# Power.net
KiCad netlist of a schematic drawn in Altium Designer
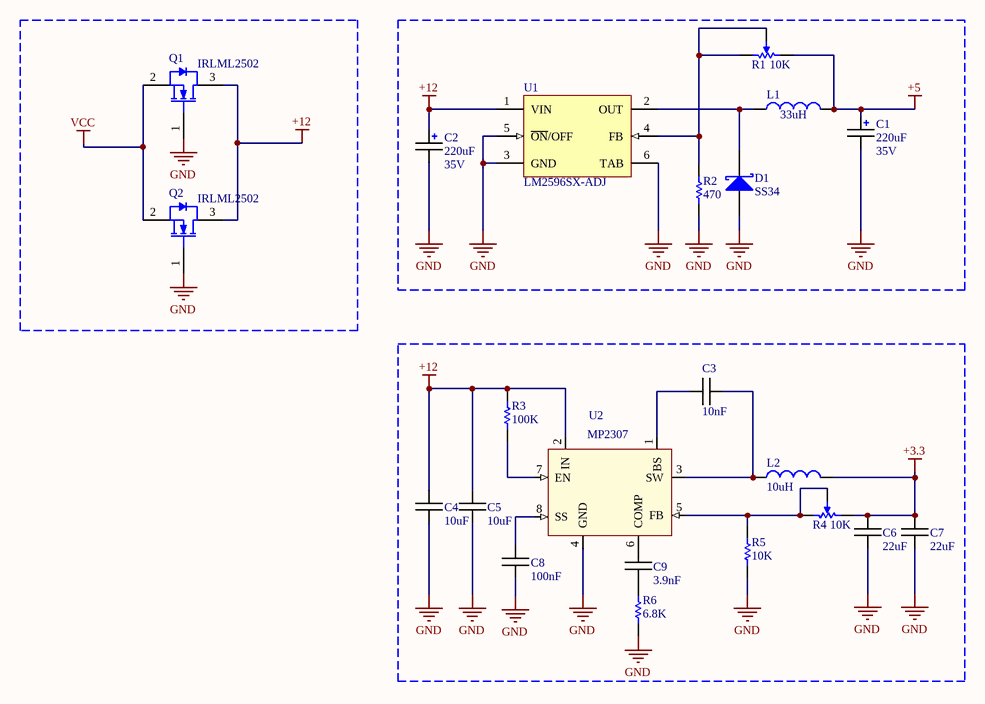
[diagram p0: Power.SchDoc]

(export (version "E")
  (design (tool "Eeschema 10.0.6"))
  (components
    (comp (ref "C1")
      (value "CAP_ELEC_SMD")
      (footprint "ECAP_SMD_8mmx10mm")
      (fields (field (name "RATED CAPACITANCE") "220uF") (field (name "RATED VOLTAGE") "35V"))
      (libsource (lib "altium-import") (part "root_3_CAP_ELEC_SMD_"))
    )
    (comp (ref "C2")
      (value "CAP_ELEC_SMD")
      (footprint "ECAP_SMD_8mmx10mm")
      (fields (field (name "RATED CAPACITANCE") "220uF") (field (name "RATED VOLTAGE") "35V"))
      (libsource (lib "altium-import") (part "root_3_CAP_ELEC_SMD_"))
    )
    (comp (ref "C3")
      (value "CAP_SMD")
      (footprint "CAP0805")
      (description "Ceramic capacitor, 0805")
      (fields (field (name "VAL") "10nF"))
      (libsource (lib "altium-import") (part "root_0_CAP_SMD_"))
    )
    (comp (ref "C4")
      (value "CAP_SMD")
      (footprint "CAPC1206(3216)170_L")
      (description "Ceramic capacitor, 0805")
      (fields (field (name "VAL") "10uF"))
      (libsource (lib "altium-import") (part "root_1_CAP_SMD_"))
    )
    (comp (ref "C5")
      (value "CAP_SMD")
      (footprint "CAPC1206(3216)170_L")
      (description "Ceramic capacitor, 0805")
      (fields (field (name "VAL") "10uF"))
      (libsource (lib "altium-import") (part "root_1_CAP_SMD_"))
    )
    (comp (ref "C6")
      (value "CAP_SMD")
      (footprint "CAPC1206(3216)170_L")
      (description "Ceramic capacitor, 0805")
      (fields (field (name "VAL") "22uF"))
      (libsource (lib "altium-import") (part "root_1_CAP_SMD_"))
    )
    (comp (ref "C7")
      (value "CAP_SMD")
      (footprint "CAPC1206(3216)170_L")
      (description "Ceramic capacitor, 0805")
      (fields (field (name "VAL") "22uF"))
      (libsource (lib "altium-import") (part "root_1_CAP_SMD_"))
    )
    (comp (ref "C8")
      (value "CAP_SMD")
      (footprint "CAP0805")
      (description "Ceramic capacitor, 0805")
      (fields (field (name "VAL") "100nF"))
      (libsource (lib "altium-import") (part "root_1_CAP_SMD_"))
    )
    (comp (ref "C9")
      (value "CAP_SMD")
      (footprint "CAP0805")
      (description "Ceramic capacitor, 0805")
      (fields (field (name "VAL") "3.9nF"))
      (libsource (lib "altium-import") (part "root_1_CAP_SMD_"))
    )
    (comp (ref "D1")
      (value "SS34")
      (footprint "DO-214")
      (description "Schottky Rectifier")
      (libsource (lib "altium-import") (part "root_1_SS34_"))
    )
    (comp (ref "L1")
      (value "~")
      (footprint "SDR1006_SMD")
      (description "Inductor for Power Circuits")
      (fields
        (field (name "INDUCTANCE") "33uH")
        (field (name "TOLERANCE") "±30%")
        (field (name "MANUFACTURER") "TDK")
      )
      (libsource (lib "altium-import") (part "root_0_Inductor power_"))
    )
    (comp (ref "L2")
      (value "10uH")
      (footprint "IHLP2525")
      (description "Inductor for Power Circuits")
      (fields (field (name "Comment") "Inductor power"))
      (libsource (lib "altium-import") (part "root_0_Inductor power_"))
    )
    (comp (ref "Q1")
      (value "IRLML2502")
      (footprint "SOT23_L")
      (description "N-Channel HEXFET(R) Power MOSFET, 20 V VDS, +/- 12 V VGS, 4.2 A, 3-Pin SOT23, RoHS, Tape and Reel")
      (fields (field (name "MANUFACTURER") "International Rectifier"))
      (libsource (lib "web.skorpio") (part "IRLML2502"))
    )
    (comp (ref "Q2")
      (value "IRLML2502")
      (footprint "SOT23_L")
      (description "N-Channel HEXFET(R) Power MOSFET, 20 V VDS, +/- 12 V VGS, 4.2 A, 3-Pin SOT23, RoHS, Tape and Reel")
      (fields (field (name "MANUFACTURER") "International Rectifier"))
      (libsource (lib "web.skorpio") (part "IRLML2502"))
    )
    (comp (ref "R1")
      (value "10K")
      (footprint "BOUR-3296W")
      (fields (field (name "Comment") "3296W"))
      (libsource (lib "altium-import") (part "root_2_mirrored_Potentiometer_"))
    )
    (comp (ref "R2")
      (value "RES_SMD")
      (footprint "RES0805")
      (fields (field (name "VAL") "470"))
      (libsource (lib "altium-import") (part "root_1_RES_SMD_"))
    )
    (comp (ref "R3")
      (value "RES_SMD")
      (footprint "RES0805")
      (fields (field (name "VAL") "100K"))
      (libsource (lib "altium-import") (part "root_1_RES_SMD_"))
    )
    (comp (ref "R4")
      (value "10K")
      (footprint "BOUR-3296W")
      (fields (field (name "Comment") "3296W"))
      (libsource (lib "altium-import") (part "root_2_mirrored_Potentiometer_"))
    )
    (comp (ref "R5")
      (value "RES_SMD")
      (footprint "RES0805")
      (fields (field (name "VAL") "10K"))
      (libsource (lib "altium-import") (part "root_1_RES_SMD_"))
    )
    (comp (ref "R6")
      (value "RES_SMD")
      (footprint "RES0805")
      (fields (field (name "VAL") "6.8K"))
      (libsource (lib "altium-import") (part "root_1_RES_SMD_"))
    )
    (comp (ref "U1")
      (value "LM2596SX-ADJ")
      (footprint "KTT0005B_N")
      (description "SIMPLE SWITCHER® Power Converter 150 KHz 3A Step-Down Voltage Regulator, 5-pin TO-263")
      (fields (field (name "MANUFACTURER") "Texas Instruments"))
      (libsource (lib "altium-import") (part "root_0_LM2596SX-ADJ_"))
    )
    (comp (ref "U2")
      (value "MP2307")
      (footprint "SOIC8N")
      (description "Monolithic synchronous buck regulator")
      (libsource (lib "altium-import") (part "root_0_MP2307_"))
    )
  )
  (nets
    (net (code "1") (name "+3.3") (class "Default")
      (node (ref "C6") (pin "2") (pinfunction "2_2") (pintype "passive"))
      (node (ref "C7") (pin "2") (pinfunction "2_2") (pintype "passive"))
      (node (ref "L2") (pin "2") (pinfunction "2_2") (pintype "passive"))
      (node (ref "R4") (pin "3") (pinfunction "3_3") (pintype "passive"))
    )
    (net (code "2") (name "+5") (class "Default")
      (node (ref "C1") (pin "1") (pinfunction "1_1") (pintype "passive"))
      (node (ref "L1") (pin "2") (pinfunction "2_2") (pintype "passive"))
      (node (ref "R1") (pin "3") (pinfunction "3_3") (pintype "passive"))
    )
    (net (code "3") (name "+12") (class "Default")
      (node (ref "C2") (pin "1") (pinfunction "1_1") (pintype "passive"))
      (node (ref "C4") (pin "2") (pinfunction "2_2") (pintype "passive"))
      (node (ref "C5") (pin "2") (pinfunction "2_2") (pintype "passive"))
      (node (ref "Q1") (pin "3") (pinfunction "D_3") (pintype "passive"))
      (node (ref "Q2") (pin "3") (pinfunction "D_3") (pintype "passive"))
      (node (ref "R3") (pin "2") (pinfunction "2_2") (pintype "passive"))
      (node (ref "U1") (pin "1") (pinfunction "VIN_1") (pintype "power_in"))
      (node (ref "U2") (pin "2") (pinfunction "IN_2") (pintype "passive"))
    )
    (net (code "4") (name "GND") (class "Default")
      (node (ref "C1") (pin "2") (pinfunction "2_2") (pintype "passive"))
      (node (ref "C2") (pin "2") (pinfunction "2_2") (pintype "passive"))
      (node (ref "C4") (pin "1") (pinfunction "1_1") (pintype "passive"))
      (node (ref "C5") (pin "1") (pinfunction "1_1") (pintype "passive"))
      (node (ref "C6") (pin "1") (pinfunction "1_1") (pintype "passive"))
      (node (ref "C7") (pin "1") (pinfunction "1_1") (pintype "passive"))
      (node (ref "C8") (pin "1") (pinfunction "1_1") (pintype "passive"))
      (node (ref "D1") (pin "2") (pinfunction "A_2") (pintype "passive"))
      (node (ref "Q1") (pin "1") (pinfunction "G_1") (pintype "passive"))
      (node (ref "Q2") (pin "1") (pinfunction "G_1") (pintype "passive"))
      (node (ref "R2") (pin "1") (pinfunction "1_1") (pintype "passive"))
      (node (ref "R5") (pin "1") (pinfunction "1_1") (pintype "passive"))
      (node (ref "R6") (pin "1") (pinfunction "1_1") (pintype "passive"))
      (node (ref "U1") (pin "3") (pinfunction "GND_3") (pintype "power_in"))
      (node (ref "U1") (pin "5") (pinfunction "~{ON}/OFF_5") (pintype "input"))
      (node (ref "U1") (pin "6") (pinfunction "TAB_6") (pintype "power_in"))
      (node (ref "U2") (pin "4") (pinfunction "GND_4") (pintype "passive"))
    )
    (net (code "5") (name "Net-(C9-Pad1)") (class "Default")
      (node (ref "C9") (pin "1") (pinfunction "1_1") (pintype "passive"))
      (node (ref "R6") (pin "2") (pinfunction "2_2") (pintype "passive"))
    )
    (net (code "6") (name "Net-(D1-K)") (class "Default")
      (node (ref "D1") (pin "1") (pinfunction "K_1") (pintype "passive"))
      (node (ref "L1") (pin "1") (pinfunction "1_1") (pintype "passive"))
      (node (ref "U1") (pin "2") (pinfunction "OUT_2") (pintype "power_in"))
    )
    (net (code "7") (name "Net-(U1-FB)") (class "Default")
      (node (ref "R1") (pin "1") (pinfunction "1_1") (pintype "passive"))
      (node (ref "R1") (pin "2") (pinfunction "2_2") (pintype "passive"))
      (node (ref "R2") (pin "2") (pinfunction "2_2") (pintype "passive"))
      (node (ref "U1") (pin "4") (pinfunction "FB_4") (pintype "input"))
    )
    (net (code "8") (name "Net-(U2-BS)") (class "Default")
      (node (ref "C3") (pin "1") (pinfunction "1_1") (pintype "passive"))
      (node (ref "U2") (pin "1") (pinfunction "BS_1") (pintype "passive"))
    )
    (net (code "9") (name "Net-(U2-COMP)") (class "Default")
      (node (ref "C9") (pin "2") (pinfunction "2_2") (pintype "passive"))
      (node (ref "U2") (pin "6") (pinfunction "COMP_6") (pintype "passive"))
    )
    (net (code "10") (name "Net-(U2-EN)") (class "Default")
      (node (ref "R3") (pin "1") (pinfunction "1_1") (pintype "passive"))
      (node (ref "U2") (pin "7") (pinfunction "EN_7") (pintype "input"))
    )
    (net (code "11") (name "Net-(U2-FB)") (class "Default")
      (node (ref "R4") (pin "1") (pinfunction "1_1") (pintype "passive"))
      (node (ref "R4") (pin "2") (pinfunction "2_2") (pintype "passive"))
      (node (ref "R5") (pin "2") (pinfunction "2_2") (pintype "passive"))
      (node (ref "U2") (pin "5") (pinfunction "FB_5") (pintype "input"))
    )
    (net (code "12") (name "Net-(U2-SS)") (class "Default")
      (node (ref "C8") (pin "2") (pinfunction "2_2") (pintype "passive"))
      (node (ref "U2") (pin "8") (pinfunction "SS_8") (pintype "input"))
    )
    (net (code "13") (name "Net-(U2-SW)") (class "Default")
      (node (ref "C3") (pin "2") (pinfunction "2_2") (pintype "passive"))
      (node (ref "L2") (pin "1") (pinfunction "1_1") (pintype "passive"))
      (node (ref "U2") (pin "3") (pinfunction "SW_3") (pintype "passive"))
    )
    (net (code "14") (name "VCC") (class "Default")
      (node (ref "Q1") (pin "2") (pinfunction "S_2") (pintype "passive"))
      (node (ref "Q2") (pin "2") (pinfunction "S_2") (pintype "passive"))
    )
  )
)
